# JediLightSwitch-V1_1.net
KiCad netlist of a schematic drawn in EAGLE
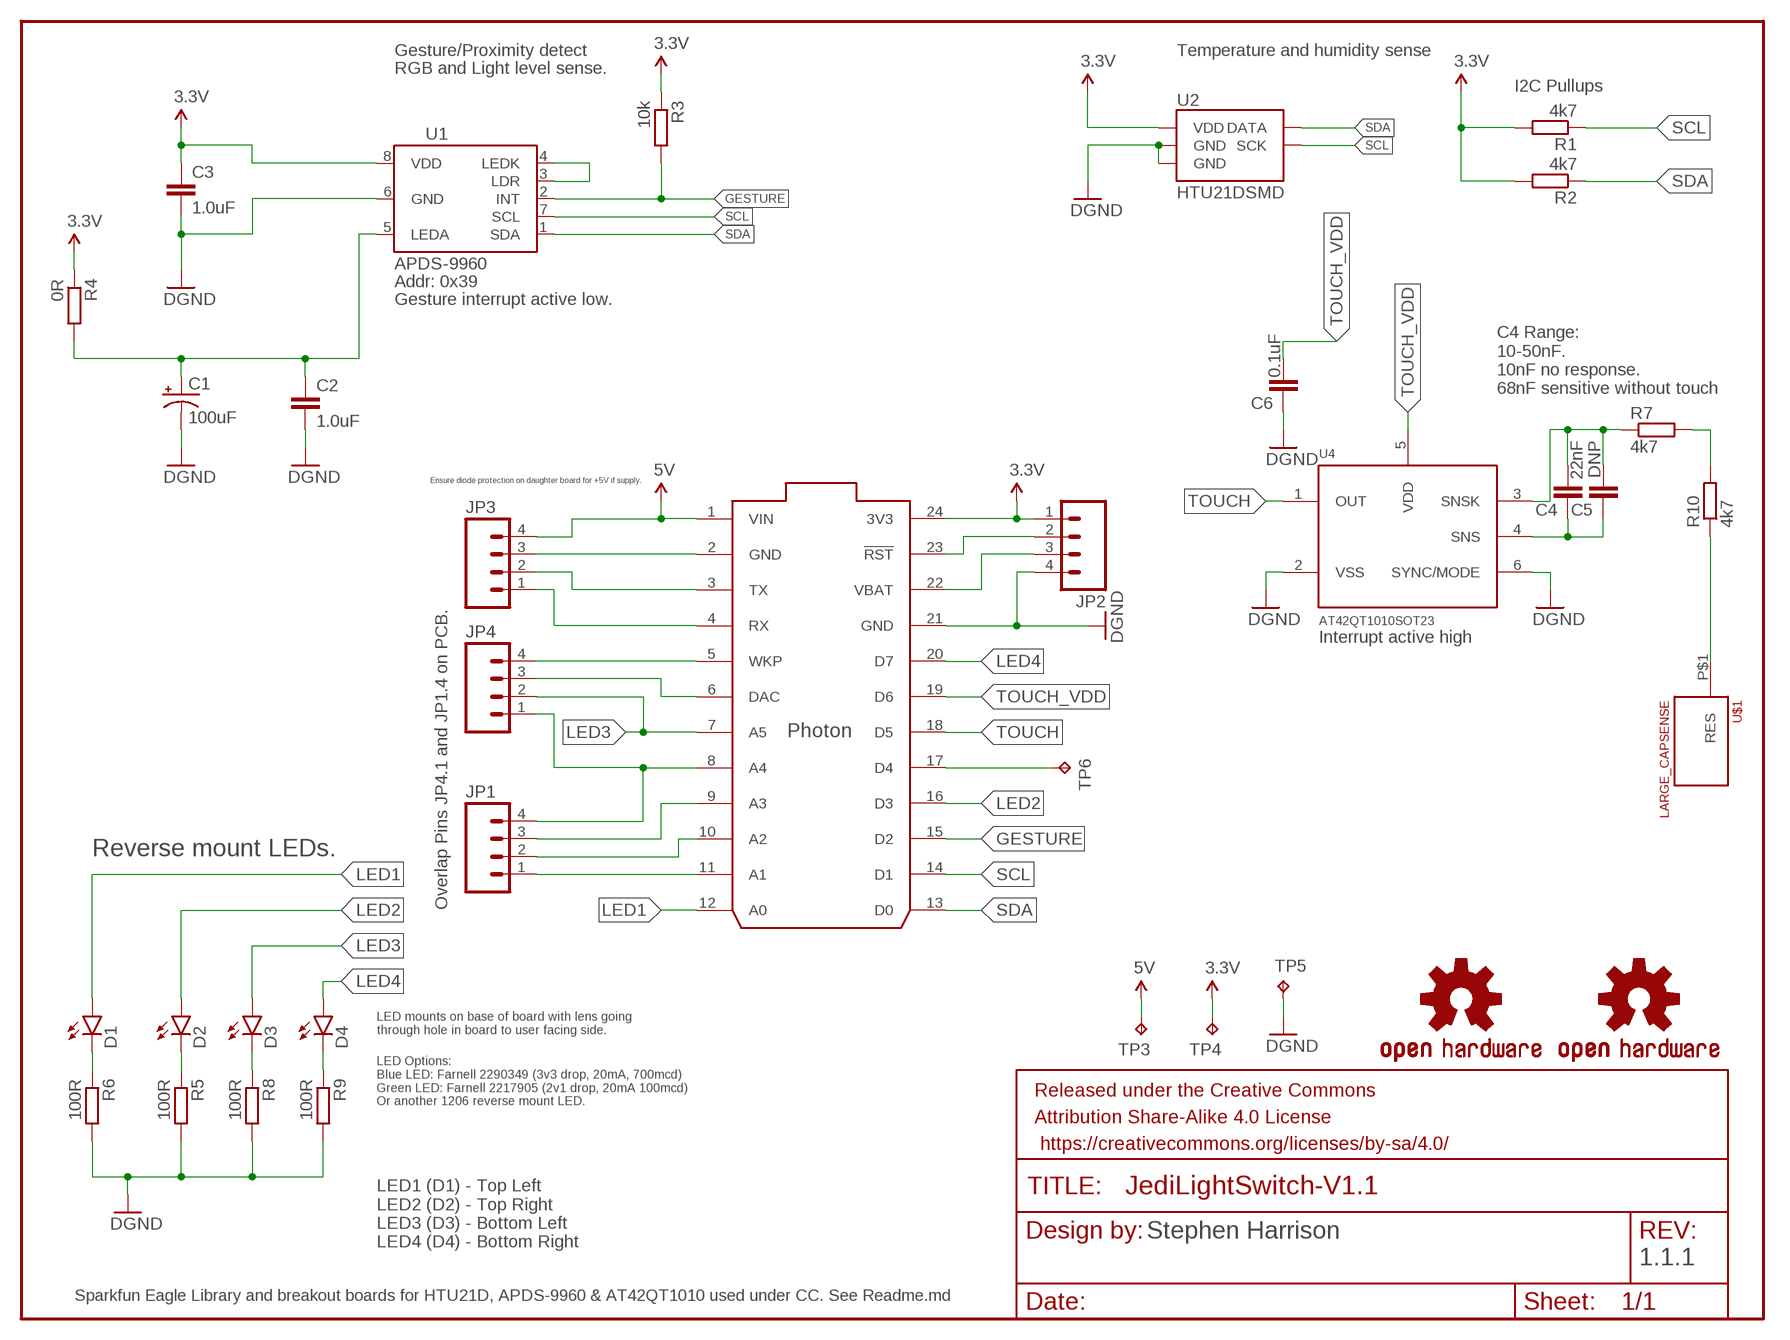
[diagram p0: schematic, sheet 1]

(export (version "E")
  (design (tool "Eeschema 10.0.6"))
  (components
    (comp (ref "C1")
      (value "100uF")
      (footprint "eagle-import:EIA7343")
      (libsource (lib "eagle-import") (part "100UF-10V-10%(TANT)"))
    )
    (comp (ref "C2")
      (value "1.0uF")
      (footprint "eagle-import:C0805")
      (libsource (lib "eagle-import") (part "C-EUC0805"))
    )
    (comp (ref "C3")
      (value "1.0uF")
      (footprint "eagle-import:C0805")
      (libsource (lib "eagle-import") (part "C-EUC0805"))
    )
    (comp (ref "C4")
      (value "22nF")
      (footprint "eagle-import:C0805")
      (libsource (lib "eagle-import") (part "C-EUC0805"))
    )
    (comp (ref "C5")
      (value "DNP")
      (footprint "eagle-import:C0805")
      (libsource (lib "eagle-import") (part "C-EUC0805"))
    )
    (comp (ref "C6")
      (value "0.1uF")
      (footprint "eagle-import:C0805")
      (libsource (lib "eagle-import") (part "C-EUC0805"))
    )
    (comp (ref "D1")
      (value "LED1206-BOTTOM")
      (footprint "eagle-import:LED-1206-BOTTOM")
      (libsource (lib "eagle-import") (part "LED1206-BOTTOM"))
    )
    (comp (ref "D2")
      (value "LED1206-BOTTOM")
      (footprint "eagle-import:LED-1206-BOTTOM")
      (libsource (lib "eagle-import") (part "LED1206-BOTTOM"))
    )
    (comp (ref "D3")
      (value "LED1206-BOTTOM")
      (footprint "eagle-import:LED-1206-BOTTOM")
      (libsource (lib "eagle-import") (part "LED1206-BOTTOM"))
    )
    (comp (ref "D4")
      (value "LED1206-BOTTOM")
      (footprint "eagle-import:LED-1206-BOTTOM")
      (libsource (lib "eagle-import") (part "LED1206-BOTTOM"))
    )
    (comp (ref "FRAME2")
      (value "FRAME-LETTER")
      (footprint "eagle-import:CREATIVE_COMMONS")
      (libsource (lib "eagle-import") (part "FRAME-LETTER"))
    )
    (comp (ref "JP1")
      (value "M04SMD_STRAIGHT_COMBO")
      (footprint "eagle-import:1X04_SMD_STRAIGHT_COMBO")
      (libsource (lib "eagle-import") (part "M04SMD_STRAIGHT_COMBO"))
    )
    (comp (ref "JP2")
      (value "M04SMD_STRAIGHT_COMBO")
      (footprint "eagle-import:1X04_SMD_STRAIGHT_COMBO")
      (libsource (lib "eagle-import") (part "M04SMD_STRAIGHT_COMBO"))
    )
    (comp (ref "JP3")
      (value "M04SMD_STRAIGHT_COMBO")
      (footprint "eagle-import:1X04_SMD_STRAIGHT_COMBO")
      (libsource (lib "eagle-import") (part "M04SMD_STRAIGHT_COMBO"))
    )
    (comp (ref "JP4")
      (value "M04SMD_STRAIGHT_COMBO")
      (footprint "eagle-import:1X04_SMD_STRAIGHT_COMBO")
      (libsource (lib "eagle-import") (part "M04SMD_STRAIGHT_COMBO"))
    )
    (comp (ref "LOGO1")
      (value "OSHW-LOGOM")
      (footprint "eagle-import:OSHW-LOGO-M")
      (libsource (lib "eagle-import") (part "OSHW-LOGOM"))
    )
    (comp (ref "LOGO2")
      (value "OSHW-LOGOM")
      (footprint "eagle-import:OSHW-LOGO-M")
      (libsource (lib "eagle-import") (part "OSHW-LOGOM"))
    )
    (comp (ref "R1")
      (value "4k7")
      (footprint "eagle-import:R0805")
      (libsource (lib "eagle-import") (part "R-EU_R0805"))
    )
    (comp (ref "R2")
      (value "4k7")
      (footprint "eagle-import:R0805")
      (libsource (lib "eagle-import") (part "R-EU_R0805"))
    )
    (comp (ref "R3")
      (value "10k")
      (footprint "eagle-import:R0805")
      (libsource (lib "eagle-import") (part "R-EU_R0805"))
    )
    (comp (ref "R4")
      (value "0R")
      (footprint "eagle-import:R0805")
      (libsource (lib "eagle-import") (part "R-EU_R0805"))
    )
    (comp (ref "R5")
      (value "100R")
      (footprint "eagle-import:R0805")
      (libsource (lib "eagle-import") (part "R-EU_R0805"))
    )
    (comp (ref "R6")
      (value "100R")
      (footprint "eagle-import:R0805")
      (libsource (lib "eagle-import") (part "R-EU_R0805"))
    )
    (comp (ref "R7")
      (value "4k7")
      (footprint "eagle-import:R0805")
      (libsource (lib "eagle-import") (part "R-EU_R0805"))
    )
    (comp (ref "R8")
      (value "100R")
      (footprint "eagle-import:R0805")
      (libsource (lib "eagle-import") (part "R-EU_R0805"))
    )
    (comp (ref "R9")
      (value "100R")
      (footprint "eagle-import:R0805")
      (libsource (lib "eagle-import") (part "R-EU_R0805"))
    )
    (comp (ref "R10")
      (value "4k7")
      (footprint "eagle-import:R0805")
      (libsource (lib "eagle-import") (part "R-EU_R0805"))
    )
    (comp (ref "TP3")
      (value "TPTP20R")
      (footprint "eagle-import:TP20R")
      (libsource (lib "eagle-import") (part "TPTP20R"))
    )
    (comp (ref "TP4")
      (value "3v3")
      (footprint "eagle-import:TP20R")
      (libsource (lib "eagle-import") (part "TPTP20R"))
    )
    (comp (ref "TP5")
      (value "TPTP20R")
      (footprint "eagle-import:TP20R")
      (libsource (lib "eagle-import") (part "TPTP20R"))
    )
    (comp (ref "TP6")
      (value "TPTP20R")
      (footprint "eagle-import:TP20R")
      (libsource (lib "eagle-import") (part "TPTP20R"))
    )
    (comp (ref "U$1")
      (value "LARGE_CAPSENSE")
      (footprint "eagle-import:LARGE_CAPSENSE")
      (libsource (lib "eagle-import") (part "LARGE_CAPSENSE"))
    )
    (comp (ref "U1")
      (value "APDS-9960")
      (footprint "eagle-import:APDS-9960")
      (libsource (lib "eagle-import") (part "APDS-9960"))
    )
    (comp (ref "U2")
      (value "HTU21DSMD")
      (footprint "eagle-import:HTU21D")
      (libsource (lib "eagle-import") (part "HTU21DSMD"))
    )
    (comp (ref "U3")
      (value "PHOTON_SMD")
      (footprint "eagle-import:PHOTON_SMD")
      (libsource (lib "eagle-import") (part "PHOTON_SMD"))
    )
    (comp (ref "U4")
      (value "AT42QT1010SOT23")
      (footprint "eagle-import:SOT23-6")
      (libsource (lib "eagle-import") (part "AT42QT1010SOT23"))
    )
  )
  (nets
    (net (code "1") (name "3.3V") (class "Default")
      (node (ref "C3") (pin "1") (pinfunction "1_1") (pintype "passive"))
      (node (ref "JP2") (pin "1") (pinfunction "1_1") (pintype "passive"))
      (node (ref "R1") (pin "2") (pinfunction "2_2") (pintype "passive"))
      (node (ref "R2") (pin "2") (pinfunction "2_2") (pintype "passive"))
      (node (ref "R3") (pin "1") (pinfunction "1_1") (pintype "passive"))
      (node (ref "R4") (pin "1") (pinfunction "1_1") (pintype "passive"))
      (node (ref "TP4") (pin "TP") (pinfunction "TP_TP") (pintype "input"))
      (node (ref "U1") (pin "8") (pinfunction "VDD_8") (pintype "bidirectional"))
      (node (ref "U2") (pin "VDD") (pinfunction "VDD_VDD") (pintype "power_in"))
      (node (ref "U3") (pin "24") (pinfunction "3V3_24") (pintype "power_in"))
    )
    (net (code "2") (name "5V") (class "Default")
      (node (ref "JP3") (pin "4") (pinfunction "4_4") (pintype "passive"))
      (node (ref "TP3") (pin "TP") (pinfunction "TP_TP") (pintype "input"))
      (node (ref "U3") (pin "1") (pinfunction "VIN_1") (pintype "power_in"))
    )
    (net (code "3") (name "DGND") (class "Default")
      (node (ref "C1") (pin "C") (pinfunction "-_C") (pintype "passive"))
      (node (ref "C2") (pin "2") (pinfunction "2_2") (pintype "passive"))
      (node (ref "C3") (pin "2") (pinfunction "2_2") (pintype "passive"))
      (node (ref "C6") (pin "1") (pinfunction "1_1") (pintype "passive"))
      (node (ref "JP2") (pin "4") (pinfunction "4_4") (pintype "passive"))
      (node (ref "JP3") (pin "3") (pinfunction "3_3") (pintype "passive"))
      (node (ref "R5") (pin "2") (pinfunction "2_2") (pintype "passive"))
      (node (ref "R6") (pin "2") (pinfunction "2_2") (pintype "passive"))
      (node (ref "R8") (pin "2") (pinfunction "2_2") (pintype "passive"))
      (node (ref "R9") (pin "2") (pinfunction "2_2") (pintype "passive"))
      (node (ref "TP5") (pin "TP") (pinfunction "TP_TP") (pintype "input"))
      (node (ref "U1") (pin "6") (pinfunction "GND_6") (pintype "bidirectional"))
      (node (ref "U2") (pin "7") (pinfunction "GND_7") (pintype "power_in"))
      (node (ref "U2") (pin "GND") (pinfunction "GND_GND") (pintype "power_in"))
      (node (ref "U3") (pin "2") (pinfunction "GND_2") (pintype "power_in"))
      (node (ref "U3") (pin "21") (pinfunction "GND_21") (pintype "power_in"))
      (node (ref "U4") (pin "2") (pinfunction "VSS_2") (pintype "bidirectional"))
      (node (ref "U4") (pin "6") (pinfunction "SYNC/MODE_6") (pintype "bidirectional"))
    )
    (net (code "4") (name "GESTURE") (class "Default")
      (node (ref "R3") (pin "2") (pinfunction "2_2") (pintype "passive"))
      (node (ref "U1") (pin "2") (pinfunction "INT_2") (pintype "bidirectional"))
      (node (ref "U3") (pin "15") (pinfunction "D2_15") (pintype "bidirectional"))
    )
    (net (code "5") (name "LED1") (class "Default")
      (node (ref "D1") (pin "A") (pinfunction "A_A") (pintype "passive"))
      (node (ref "U3") (pin "12") (pinfunction "A0_12") (pintype "bidirectional"))
    )
    (net (code "6") (name "LED2") (class "Default")
      (node (ref "D2") (pin "A") (pinfunction "A_A") (pintype "passive"))
      (node (ref "U3") (pin "16") (pinfunction "D3_16") (pintype "bidirectional"))
    )
    (net (code "7") (name "LED3") (class "Default")
      (node (ref "D3") (pin "A") (pinfunction "A_A") (pintype "passive"))
      (node (ref "JP4") (pin "2") (pinfunction "2_2") (pintype "passive"))
      (node (ref "U3") (pin "7") (pinfunction "A5_7") (pintype "bidirectional"))
    )
    (net (code "8") (name "LED4") (class "Default")
      (node (ref "D4") (pin "A") (pinfunction "A_A") (pintype "passive"))
      (node (ref "U3") (pin "20") (pinfunction "D7_20") (pintype "bidirectional"))
    )
    (net (code "9") (name "Net-(C1-+)") (class "Default")
      (node (ref "C1") (pin "A") (pinfunction "+_A") (pintype "passive"))
      (node (ref "C2") (pin "1") (pinfunction "1_1") (pintype "passive"))
      (node (ref "R4") (pin "2") (pinfunction "2_2") (pintype "passive"))
      (node (ref "U1") (pin "5") (pinfunction "LEDA_5") (pintype "bidirectional"))
    )
    (net (code "10") (name "Net-(D1-PadC)") (class "Default")
      (node (ref "D1") (pin "C") (pinfunction "C_C") (pintype "passive"))
      (node (ref "R6") (pin "1") (pinfunction "1_1") (pintype "passive"))
    )
    (net (code "11") (name "Net-(D2-PadC)") (class "Default")
      (node (ref "D2") (pin "C") (pinfunction "C_C") (pintype "passive"))
      (node (ref "R5") (pin "1") (pinfunction "1_1") (pintype "passive"))
    )
    (net (code "12") (name "Net-(D3-PadC)") (class "Default")
      (node (ref "D3") (pin "C") (pinfunction "C_C") (pintype "passive"))
      (node (ref "R8") (pin "1") (pinfunction "1_1") (pintype "passive"))
    )
    (net (code "13") (name "Net-(D4-PadC)") (class "Default")
      (node (ref "D4") (pin "C") (pinfunction "C_C") (pintype "passive"))
      (node (ref "R9") (pin "1") (pinfunction "1_1") (pintype "passive"))
    )
    (net (code "14") (name "Net-(R10-Pad2)") (class "Default")
      (node (ref "R10") (pin "2") (pinfunction "2_2") (pintype "passive"))
      (node (ref "R7") (pin "2") (pinfunction "2_2") (pintype "passive"))
    )
    (net (code "15") (name "Net-(U$1-RES)") (class "Default")
      (node (ref "R10") (pin "1") (pinfunction "1_1") (pintype "passive"))
      (node (ref "U$1") (pin "P$1") (pinfunction "RES_P$1") (pintype "bidirectional"))
    )
    (net (code "16") (name "Net-(U1-LDR)") (class "Default")
      (node (ref "U1") (pin "3") (pinfunction "LDR_3") (pintype "bidirectional"))
      (node (ref "U1") (pin "4") (pinfunction "LEDK_4") (pintype "bidirectional"))
    )
    (net (code "17") (name "Net-(U3A-A1)") (class "Default")
      (node (ref "JP1") (pin "1") (pinfunction "1_1") (pintype "passive"))
      (node (ref "U3") (pin "11") (pinfunction "A1_11") (pintype "bidirectional"))
    )
    (net (code "18") (name "Net-(U3A-A2)") (class "Default")
      (node (ref "JP1") (pin "2") (pinfunction "2_2") (pintype "passive"))
      (node (ref "U3") (pin "10") (pinfunction "A2_10") (pintype "bidirectional"))
    )
    (net (code "19") (name "Net-(U3A-A3)") (class "Default")
      (node (ref "JP1") (pin "3") (pinfunction "3_3") (pintype "passive"))
      (node (ref "U3") (pin "9") (pinfunction "A3_9") (pintype "bidirectional"))
    )
    (net (code "20") (name "Net-(U3A-A4)") (class "Default")
      (node (ref "JP1") (pin "4") (pinfunction "4_4") (pintype "passive"))
      (node (ref "JP4") (pin "1") (pinfunction "1_1") (pintype "passive"))
      (node (ref "U3") (pin "8") (pinfunction "A4_8") (pintype "bidirectional"))
    )
    (net (code "21") (name "Net-(U3A-D4)") (class "Default")
      (node (ref "TP6") (pin "TP") (pinfunction "TP_TP") (pintype "input"))
      (node (ref "U3") (pin "17") (pinfunction "D4_17") (pintype "bidirectional"))
    )
    (net (code "22") (name "Net-(U3A-DAC)") (class "Default")
      (node (ref "JP4") (pin "3") (pinfunction "3_3") (pintype "passive"))
      (node (ref "U3") (pin "6") (pinfunction "DAC_6") (pintype "bidirectional"))
    )
    (net (code "23") (name "Net-(U3A-RX)") (class "Default")
      (node (ref "JP3") (pin "1") (pinfunction "1_1") (pintype "passive"))
      (node (ref "U3") (pin "4") (pinfunction "RX_4") (pintype "bidirectional"))
    )
    (net (code "24") (name "Net-(U3A-TX)") (class "Default")
      (node (ref "JP3") (pin "2") (pinfunction "2_2") (pintype "passive"))
      (node (ref "U3") (pin "3") (pinfunction "TX_3") (pintype "bidirectional"))
    )
    (net (code "25") (name "Net-(U3A-VBAT)") (class "Default")
      (node (ref "JP2") (pin "3") (pinfunction "3_3") (pintype "passive"))
      (node (ref "U3") (pin "22") (pinfunction "VBAT_22") (pintype "power_in"))
    )
    (net (code "26") (name "Net-(U3A-WKP)") (class "Default")
      (node (ref "JP4") (pin "4") (pinfunction "4_4") (pintype "passive"))
      (node (ref "U3") (pin "5") (pinfunction "WKP_5") (pintype "bidirectional"))
    )
    (net (code "27") (name "Net-(U3A-~{RST})") (class "Default")
      (node (ref "JP2") (pin "2") (pinfunction "2_2") (pintype "passive"))
      (node (ref "U3") (pin "23") (pinfunction "~{RST}_23") (pintype "bidirectional"))
    )
    (net (code "28") (name "Net-(U4-SNS)") (class "Default")
      (node (ref "C4") (pin "1") (pinfunction "1_1") (pintype "passive"))
      (node (ref "C5") (pin "1") (pinfunction "1_1") (pintype "passive"))
      (node (ref "U4") (pin "4") (pinfunction "SNS_4") (pintype "bidirectional"))
    )
    (net (code "29") (name "Net-(U4-SNSK)") (class "Default")
      (node (ref "C4") (pin "2") (pinfunction "2_2") (pintype "passive"))
      (node (ref "C5") (pin "2") (pinfunction "2_2") (pintype "passive"))
      (node (ref "R7") (pin "1") (pinfunction "1_1") (pintype "passive"))
      (node (ref "U4") (pin "3") (pinfunction "SNSK_3") (pintype "bidirectional"))
    )
    (net (code "30") (name "SCL") (class "Default")
      (node (ref "R1") (pin "1") (pinfunction "1_1") (pintype "passive"))
      (node (ref "U1") (pin "7") (pinfunction "SCL_7") (pintype "bidirectional"))
      (node (ref "U2") (pin "SCK") (pinfunction "SCK_SCK") (pintype "input"))
      (node (ref "U3") (pin "14") (pinfunction "D1_14") (pintype "bidirectional"))
    )
    (net (code "31") (name "SDA") (class "Default")
      (node (ref "R2") (pin "1") (pinfunction "1_1") (pintype "passive"))
      (node (ref "U1") (pin "1") (pinfunction "SDA_1") (pintype "bidirectional"))
      (node (ref "U2") (pin "DATA") (pinfunction "DATA_DATA") (pintype "bidirectional"))
      (node (ref "U3") (pin "13") (pinfunction "D0_13") (pintype "bidirectional"))
    )
    (net (code "32") (name "TOUCH") (class "Default")
      (node (ref "U3") (pin "18") (pinfunction "D5_18") (pintype "bidirectional"))
      (node (ref "U4") (pin "1") (pinfunction "OUT_1") (pintype "bidirectional"))
    )
    (net (code "33") (name "TOUCH_VDD") (class "Default")
      (node (ref "C6") (pin "2") (pinfunction "2_2") (pintype "passive"))
      (node (ref "U3") (pin "19") (pinfunction "D6_19") (pintype "bidirectional"))
      (node (ref "U4") (pin "5") (pinfunction "VDD_5") (pintype "bidirectional"))
    )
  )
)
